# POWER.net
KiCad netlist of a schematic drawn in Altium Designer
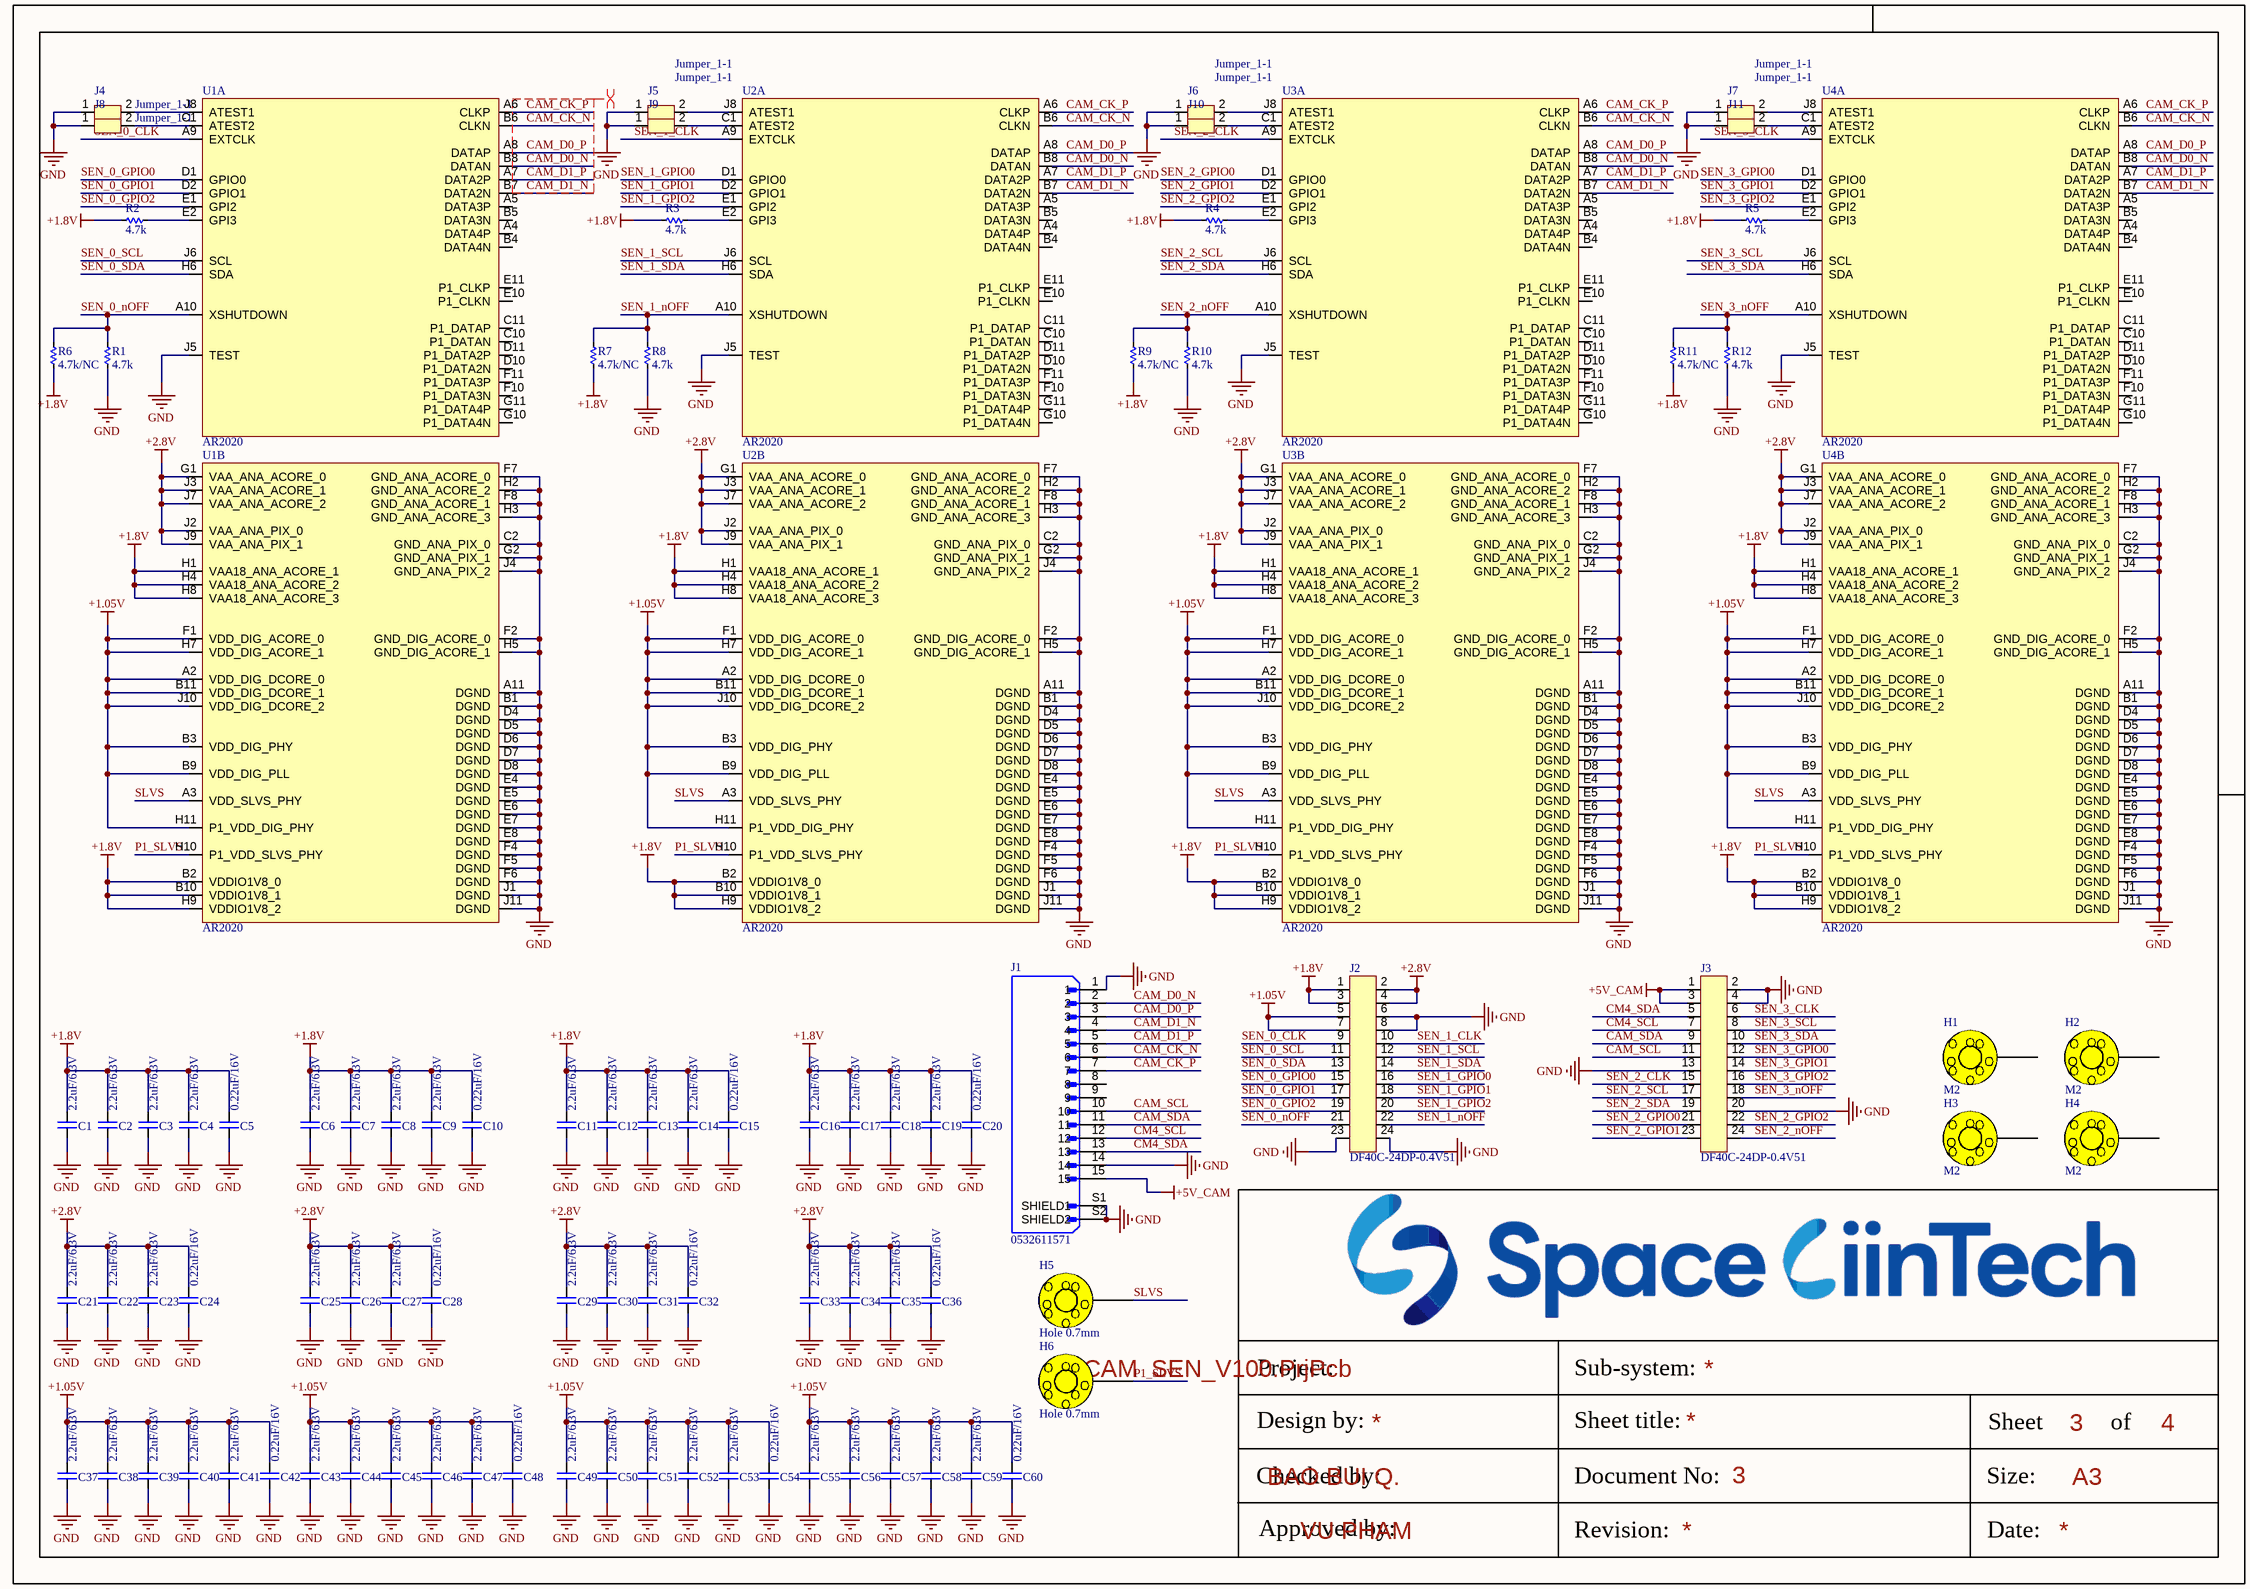
[diagram p0: POWER.SchDoc]

(export (version "E")
  (design (tool "Eeschema 10.0.6"))
  (components
    (comp (ref "C1")
      (value "2.2uF/6.3V")
      (footprint "CAP_C_1005X60")
      (description "CAP_Chip")
      (libsource (lib "LABLIB") (part "CAP_SMD"))
    )
    (comp (ref "C2")
      (value "2.2uF/6.3V")
      (footprint "CAP_C_1005X60")
      (description "CAP_Chip")
      (libsource (lib "LABLIB") (part "CAP_SMD"))
    )
    (comp (ref "C3")
      (value "2.2uF/6.3V")
      (footprint "CAP_C_1005X60")
      (description "CAP_Chip")
      (libsource (lib "LABLIB") (part "CAP_SMD"))
    )
    (comp (ref "C4")
      (value "2.2uF/6.3V")
      (footprint "CAP_C_1005X60")
      (description "CAP_Chip")
      (libsource (lib "LABLIB") (part "CAP_SMD"))
    )
    (comp (ref "C5")
      (value "0.22uF/16V")
      (footprint "CAP_C_1005X60")
      (description "CAP_Chip")
      (libsource (lib "LABLIB") (part "CAP_SMD"))
    )
    (comp (ref "C6")
      (value "2.2uF/6.3V")
      (footprint "CAP_C_1005X60")
      (description "CAP_Chip")
      (libsource (lib "LABLIB") (part "CAP_SMD"))
    )
    (comp (ref "C7")
      (value "2.2uF/6.3V")
      (footprint "CAP_C_1005X60")
      (description "CAP_Chip")
      (libsource (lib "LABLIB") (part "CAP_SMD"))
    )
    (comp (ref "C8")
      (value "2.2uF/6.3V")
      (footprint "CAP_C_1005X60")
      (description "CAP_Chip")
      (libsource (lib "LABLIB") (part "CAP_SMD"))
    )
    (comp (ref "C9")
      (value "2.2uF/6.3V")
      (footprint "CAP_C_1005X60")
      (description "CAP_Chip")
      (libsource (lib "LABLIB") (part "CAP_SMD"))
    )
    (comp (ref "C10")
      (value "0.22uF/16V")
      (footprint "CAP_C_1005X60")
      (description "CAP_Chip")
      (libsource (lib "LABLIB") (part "CAP_SMD"))
    )
    (comp (ref "C11")
      (value "2.2uF/6.3V")
      (footprint "CAP_C_1005X60")
      (description "CAP_Chip")
      (libsource (lib "LABLIB") (part "CAP_SMD"))
    )
    (comp (ref "C12")
      (value "2.2uF/6.3V")
      (footprint "CAP_C_1005X60")
      (description "CAP_Chip")
      (libsource (lib "LABLIB") (part "CAP_SMD"))
    )
    (comp (ref "C13")
      (value "2.2uF/6.3V")
      (footprint "CAP_C_1005X60")
      (description "CAP_Chip")
      (libsource (lib "LABLIB") (part "CAP_SMD"))
    )
    (comp (ref "C14")
      (value "2.2uF/6.3V")
      (footprint "CAP_C_1005X60")
      (description "CAP_Chip")
      (libsource (lib "LABLIB") (part "CAP_SMD"))
    )
    (comp (ref "C15")
      (value "0.22uF/16V")
      (footprint "CAP_C_1005X60")
      (description "CAP_Chip")
      (libsource (lib "LABLIB") (part "CAP_SMD"))
    )
    (comp (ref "C16")
      (value "2.2uF/6.3V")
      (footprint "CAP_C_1005X60")
      (description "CAP_Chip")
      (libsource (lib "LABLIB") (part "CAP_SMD"))
    )
    (comp (ref "C17")
      (value "2.2uF/6.3V")
      (footprint "CAP_C_1005X60")
      (description "CAP_Chip")
      (libsource (lib "LABLIB") (part "CAP_SMD"))
    )
    (comp (ref "C18")
      (value "2.2uF/6.3V")
      (footprint "CAP_C_1005X60")
      (description "CAP_Chip")
      (libsource (lib "LABLIB") (part "CAP_SMD"))
    )
    (comp (ref "C19")
      (value "2.2uF/6.3V")
      (footprint "CAP_C_1005X60")
      (description "CAP_Chip")
      (libsource (lib "LABLIB") (part "CAP_SMD"))
    )
    (comp (ref "C20")
      (value "0.22uF/16V")
      (footprint "CAP_C_1005X60")
      (description "CAP_Chip")
      (libsource (lib "LABLIB") (part "CAP_SMD"))
    )
    (comp (ref "C21")
      (value "2.2uF/6.3V")
      (footprint "CAP_C_1005X60")
      (description "CAP_Chip")
      (libsource (lib "LABLIB") (part "CAP_SMD"))
    )
    (comp (ref "C22")
      (value "2.2uF/6.3V")
      (footprint "CAP_C_1005X60")
      (description "CAP_Chip")
      (libsource (lib "LABLIB") (part "CAP_SMD"))
    )
    (comp (ref "C23")
      (value "2.2uF/6.3V")
      (footprint "CAP_C_1005X60")
      (description "CAP_Chip")
      (libsource (lib "LABLIB") (part "CAP_SMD"))
    )
    (comp (ref "C24")
      (value "0.22uF/16V")
      (footprint "CAP_C_1005X60")
      (description "CAP_Chip")
      (libsource (lib "LABLIB") (part "CAP_SMD"))
    )
    (comp (ref "C25")
      (value "2.2uF/6.3V")
      (footprint "CAP_C_1005X60")
      (description "CAP_Chip")
      (libsource (lib "LABLIB") (part "CAP_SMD"))
    )
    (comp (ref "C26")
      (value "2.2uF/6.3V")
      (footprint "CAP_C_1005X60")
      (description "CAP_Chip")
      (libsource (lib "LABLIB") (part "CAP_SMD"))
    )
    (comp (ref "C27")
      (value "2.2uF/6.3V")
      (footprint "CAP_C_1005X60")
      (description "CAP_Chip")
      (libsource (lib "LABLIB") (part "CAP_SMD"))
    )
    (comp (ref "C28")
      (value "0.22uF/16V")
      (footprint "CAP_C_1005X60")
      (description "CAP_Chip")
      (libsource (lib "LABLIB") (part "CAP_SMD"))
    )
    (comp (ref "C29")
      (value "2.2uF/6.3V")
      (footprint "CAP_C_1005X60")
      (description "CAP_Chip")
      (libsource (lib "LABLIB") (part "CAP_SMD"))
    )
    (comp (ref "C30")
      (value "2.2uF/6.3V")
      (footprint "CAP_C_1005X60")
      (description "CAP_Chip")
      (libsource (lib "LABLIB") (part "CAP_SMD"))
    )
    (comp (ref "C31")
      (value "2.2uF/6.3V")
      (footprint "CAP_C_1005X60")
      (description "CAP_Chip")
      (libsource (lib "LABLIB") (part "CAP_SMD"))
    )
    (comp (ref "C32")
      (value "0.22uF/16V")
      (footprint "CAP_C_1005X60")
      (description "CAP_Chip")
      (libsource (lib "LABLIB") (part "CAP_SMD"))
    )
    (comp (ref "C33")
      (value "2.2uF/6.3V")
      (footprint "CAP_C_1005X60")
      (description "CAP_Chip")
      (libsource (lib "LABLIB") (part "CAP_SMD"))
    )
    (comp (ref "C34")
      (value "2.2uF/6.3V")
      (footprint "CAP_C_1005X60")
      (description "CAP_Chip")
      (libsource (lib "LABLIB") (part "CAP_SMD"))
    )
    (comp (ref "C35")
      (value "2.2uF/6.3V")
      (footprint "CAP_C_1005X60")
      (description "CAP_Chip")
      (libsource (lib "LABLIB") (part "CAP_SMD"))
    )
    (comp (ref "C36")
      (value "0.22uF/16V")
      (footprint "CAP_C_1005X60")
      (description "CAP_Chip")
      (libsource (lib "LABLIB") (part "CAP_SMD"))
    )
    (comp (ref "C37")
      (value "2.2uF/6.3V")
      (footprint "CAP_C_1005X60")
      (description "CAP_Chip")
      (libsource (lib "LABLIB") (part "CAP_SMD"))
    )
    (comp (ref "C38")
      (value "2.2uF/6.3V")
      (footprint "CAP_C_1005X60")
      (description "CAP_Chip")
      (libsource (lib "LABLIB") (part "CAP_SMD"))
    )
    (comp (ref "C39")
      (value "2.2uF/6.3V")
      (footprint "CAP_C_1005X60")
      (description "CAP_Chip")
      (libsource (lib "LABLIB") (part "CAP_SMD"))
    )
    (comp (ref "C40")
      (value "2.2uF/6.3V")
      (footprint "CAP_C_1005X60")
      (description "CAP_Chip")
      (libsource (lib "LABLIB") (part "CAP_SMD"))
    )
    (comp (ref "C41")
      (value "2.2uF/6.3V")
      (footprint "CAP_C_1005X60")
      (description "CAP_Chip")
      (libsource (lib "LABLIB") (part "CAP_SMD"))
    )
    (comp (ref "C42")
      (value "0.22uF/16V")
      (footprint "CAP_C_1005X60")
      (description "CAP_Chip")
      (libsource (lib "LABLIB") (part "CAP_SMD"))
    )
    (comp (ref "C43")
      (value "2.2uF/6.3V")
      (footprint "CAP_C_1005X60")
      (description "CAP_Chip")
      (libsource (lib "LABLIB") (part "CAP_SMD"))
    )
    (comp (ref "C44")
      (value "2.2uF/6.3V")
      (footprint "CAP_C_1005X60")
      (description "CAP_Chip")
      (libsource (lib "LABLIB") (part "CAP_SMD"))
    )
    (comp (ref "C45")
      (value "2.2uF/6.3V")
      (footprint "CAP_C_1005X60")
      (description "CAP_Chip")
      (libsource (lib "LABLIB") (part "CAP_SMD"))
    )
    (comp (ref "C46")
      (value "2.2uF/6.3V")
      (footprint "CAP_C_1005X60")
      (description "CAP_Chip")
      (libsource (lib "LABLIB") (part "CAP_SMD"))
    )
    (comp (ref "C47")
      (value "2.2uF/6.3V")
      (footprint "CAP_C_1005X60")
      (description "CAP_Chip")
      (libsource (lib "LABLIB") (part "CAP_SMD"))
    )
    (comp (ref "C48")
      (value "0.22uF/16V")
      (footprint "CAP_C_1005X60")
      (description "CAP_Chip")
      (libsource (lib "LABLIB") (part "CAP_SMD"))
    )
    (comp (ref "C49")
      (value "2.2uF/6.3V")
      (footprint "CAP_C_1005X60")
      (description "CAP_Chip")
      (libsource (lib "LABLIB") (part "CAP_SMD"))
    )
    (comp (ref "C50")
      (value "2.2uF/6.3V")
      (footprint "CAP_C_1005X60")
      (description "CAP_Chip")
      (libsource (lib "LABLIB") (part "CAP_SMD"))
    )
    (comp (ref "C51")
      (value "2.2uF/6.3V")
      (footprint "CAP_C_1005X60")
      (description "CAP_Chip")
      (libsource (lib "LABLIB") (part "CAP_SMD"))
    )
    (comp (ref "C52")
      (value "2.2uF/6.3V")
      (footprint "CAP_C_1005X60")
      (description "CAP_Chip")
      (libsource (lib "LABLIB") (part "CAP_SMD"))
    )
    (comp (ref "C53")
      (value "2.2uF/6.3V")
      (footprint "CAP_C_1005X60")
      (description "CAP_Chip")
      (libsource (lib "LABLIB") (part "CAP_SMD"))
    )
    (comp (ref "C54")
      (value "0.22uF/16V")
      (footprint "CAP_C_1005X60")
      (description "CAP_Chip")
      (libsource (lib "LABLIB") (part "CAP_SMD"))
    )
    (comp (ref "C55")
      (value "2.2uF/6.3V")
      (footprint "CAP_C_1005X60")
      (description "CAP_Chip")
      (libsource (lib "LABLIB") (part "CAP_SMD"))
    )
    (comp (ref "C56")
      (value "2.2uF/6.3V")
      (footprint "CAP_C_1005X60")
      (description "CAP_Chip")
      (libsource (lib "LABLIB") (part "CAP_SMD"))
    )
    (comp (ref "C57")
      (value "2.2uF/6.3V")
      (footprint "CAP_C_1005X60")
      (description "CAP_Chip")
      (libsource (lib "LABLIB") (part "CAP_SMD"))
    )
    (comp (ref "C58")
      (value "2.2uF/6.3V")
      (footprint "CAP_C_1005X60")
      (description "CAP_Chip")
      (libsource (lib "LABLIB") (part "CAP_SMD"))
    )
    (comp (ref "C59")
      (value "2.2uF/6.3V")
      (footprint "CAP_C_1005X60")
      (description "CAP_Chip")
      (libsource (lib "LABLIB") (part "CAP_SMD"))
    )
    (comp (ref "C60")
      (value "0.22uF/16V")
      (footprint "CAP_C_1005X60")
      (description "CAP_Chip")
      (libsource (lib "LABLIB") (part "CAP_SMD"))
    )
    (comp (ref "H1") (value "M2") (footprint "HEX-2.2mm") (libsource (lib "hex_M3") (part "HEX-M3")))
    (comp (ref "H2") (value "M2") (footprint "HEX-2.2mm") (libsource (lib "hex_M3") (part "HEX-M3")))
    (comp (ref "H3") (value "M2") (footprint "HEX-2.2mm") (libsource (lib "hex_M3") (part "HEX-M3")))
    (comp (ref "H4") (value "M2") (footprint "HEX-2.2mm") (libsource (lib "hex_M3") (part "HEX-M3")))
    (comp (ref "H5") (value "Hole 0.7mm") (footprint "HEX-0.7mm") (libsource (lib "hex_M3") (part "HEX-M3")))
    (comp (ref "H6") (value "Hole 0.7mm") (footprint "HEX-0.7mm") (libsource (lib "hex_M3") (part "HEX-M3")))
    (comp (ref "J1")
      (value "0532611571")
      (footprint "0532611571")
      (description "Conn Shrouded Header (4 Sides) HDR 15 POS 1.25mm Solder RA Side Entry SMD PicoBladeâ„¢ T/R")
      (fields (field (name "MP") "532611571") (field (name "MF") "Molex"))
      (libsource (lib "EXP_HW_V2") (part "CONN_SMD_15"))
    )
    (comp (ref "J2")
      (value "DF40C-24DP-0.4V51")
      (footprint "CONN24_6p32X1p85")
      (description "No Description Available")
      (libsource (lib "CAMERA_SchLib") (part "DF40C-24DP-0.4V51"))
    )
    (comp (ref "J3")
      (value "DF40C-24DP-0.4V51")
      (footprint "CONN24_6p32X1p85")
      (description "No Description Available")
      (libsource (lib "CAMERA_SchLib") (part "DF40C-24DP-0.4V51"))
    )
    (comp (ref "J4")
      (value "Jumper_1-1")
      (footprint "Jumper_1-1")
      (libsource (lib "CAMERA_SchLib") (part "Jumper_1_1"))
    )
    (comp (ref "J5")
      (value "Jumper_1-1")
      (footprint "Jumper_1-1")
      (libsource (lib "CAMERA_SchLib") (part "Jumper_1_1"))
    )
    (comp (ref "J6")
      (value "Jumper_1-1")
      (footprint "Jumper_1-1")
      (libsource (lib "CAMERA_SchLib") (part "Jumper_1_1"))
    )
    (comp (ref "J7")
      (value "Jumper_1-1")
      (footprint "Jumper_1-1")
      (libsource (lib "CAMERA_SchLib") (part "Jumper_1_1"))
    )
    (comp (ref "J8")
      (value "Jumper_1-1")
      (footprint "Jumper_1-1")
      (libsource (lib "CAMERA_SchLib") (part "Jumper_1_1"))
    )
    (comp (ref "J9")
      (value "Jumper_1-1")
      (footprint "Jumper_1-1")
      (libsource (lib "CAMERA_SchLib") (part "Jumper_1_1"))
    )
    (comp (ref "J10")
      (value "Jumper_1-1")
      (footprint "Jumper_1-1")
      (libsource (lib "CAMERA_SchLib") (part "Jumper_1_1"))
    )
    (comp (ref "J11")
      (value "Jumper_1-1")
      (footprint "Jumper_1-1")
      (libsource (lib "CAMERA_SchLib") (part "Jumper_1_1"))
    )
    (comp (ref "R1")
      (value "4.7k")
      (footprint "RES_C_1005X40")
      (description "RES-Chip")
      (fields
        (field (name "MANUFACTURER") "Generic Components")
        (field (name "PUBLISHER") "Altium Hobart Technology Centre")
      )
      (libsource (lib "LABLIB") (part "RES-SMD"))
    )
    (comp (ref "R2")
      (value "4.7k")
      (footprint "RES_C_1005X40")
      (description "RES-Chip")
      (fields
        (field (name "MANUFACTURER") "Generic Components")
        (field (name "PUBLISHER") "Altium Hobart Technology Centre")
      )
      (libsource (lib "LABLIB") (part "RES-SMD"))
    )
    (comp (ref "R3")
      (value "4.7k")
      (footprint "RES_C_1005X40")
      (description "RES-Chip")
      (fields
        (field (name "MANUFACTURER") "Generic Components")
        (field (name "PUBLISHER") "Altium Hobart Technology Centre")
      )
      (libsource (lib "LABLIB") (part "RES-SMD"))
    )
    (comp (ref "R4")
      (value "4.7k")
      (footprint "RES_C_1005X40")
      (description "RES-Chip")
      (fields
        (field (name "MANUFACTURER") "Generic Components")
        (field (name "PUBLISHER") "Altium Hobart Technology Centre")
      )
      (libsource (lib "LABLIB") (part "RES-SMD"))
    )
    (comp (ref "R5")
      (value "4.7k")
      (footprint "RES_C_1005X40")
      (description "RES-Chip")
      (fields
        (field (name "MANUFACTURER") "Generic Components")
        (field (name "PUBLISHER") "Altium Hobart Technology Centre")
      )
      (libsource (lib "LABLIB") (part "RES-SMD"))
    )
    (comp (ref "R6")
      (value "4.7k/NC")
      (footprint "RES_C_1005X40")
      (description "RES-Chip")
      (fields
        (field (name "MANUFACTURER") "Generic Components")
        (field (name "PUBLISHER") "Altium Hobart Technology Centre")
      )
      (libsource (lib "LABLIB") (part "RES-SMD"))
    )
    (comp (ref "R7")
      (value "4.7k/NC")
      (footprint "RES_C_1005X40")
      (description "RES-Chip")
      (fields
        (field (name "MANUFACTURER") "Generic Components")
        (field (name "PUBLISHER") "Altium Hobart Technology Centre")
      )
      (libsource (lib "LABLIB") (part "RES-SMD"))
    )
    (comp (ref "R8")
      (value "4.7k")
      (footprint "RES_C_1005X40")
      (description "RES-Chip")
      (fields
        (field (name "MANUFACTURER") "Generic Components")
        (field (name "PUBLISHER") "Altium Hobart Technology Centre")
      )
      (libsource (lib "LABLIB") (part "RES-SMD"))
    )
    (comp (ref "R9")
      (value "4.7k/NC")
      (footprint "RES_C_1005X40")
      (description "RES-Chip")
      (fields
        (field (name "MANUFACTURER") "Generic Components")
        (field (name "PUBLISHER") "Altium Hobart Technology Centre")
      )
      (libsource (lib "LABLIB") (part "RES-SMD"))
    )
    (comp (ref "R10")
      (value "4.7k")
      (footprint "RES_C_1005X40")
      (description "RES-Chip")
      (fields
        (field (name "MANUFACTURER") "Generic Components")
        (field (name "PUBLISHER") "Altium Hobart Technology Centre")
      )
      (libsource (lib "LABLIB") (part "RES-SMD"))
    )
    (comp (ref "R11")
      (value "4.7k/NC")
      (footprint "RES_C_1005X40")
      (description "RES-Chip")
      (fields
        (field (name "MANUFACTURER") "Generic Components")
        (field (name "PUBLISHER") "Altium Hobart Technology Centre")
      )
      (libsource (lib "LABLIB") (part "RES-SMD"))
    )
    (comp (ref "R12")
      (value "4.7k")
      (footprint "RES_C_1005X40")
      (description "RES-Chip")
      (fields
        (field (name "MANUFACTURER") "Generic Components")
        (field (name "PUBLISHER") "Altium Hobart Technology Centre")
      )
      (libsource (lib "LABLIB") (part "RES-SMD"))
    )
    (comp (ref "U1")
      (value "AR2020")
      (footprint "BGA78C100P11X9_1300X1050X210")
      (libsource (lib "CAMERA_SchLib") (part "AR2020"))
    )
    (comp (ref "U2")
      (value "AR2020")
      (footprint "BGA78C100P11X9_1300X1050X210")
      (libsource (lib "CAMERA_SchLib") (part "AR2020"))
    )
    (comp (ref "U3")
      (value "AR2020")
      (footprint "BGA78C100P11X9_1300X1050X210")
      (libsource (lib "CAMERA_SchLib") (part "AR2020"))
    )
    (comp (ref "U4")
      (value "AR2020")
      (footprint "BGA78C100P11X9_1300X1050X210")
      (libsource (lib "CAMERA_SchLib") (part "AR2020"))
    )
  )
  (nets
    (net (code "1") (name "+1.05V") (class "Default")
      (node (ref "C37") (pin "2") (pinfunction "2_2") (pintype "passive"))
      (node (ref "C38") (pin "2") (pinfunction "2_2") (pintype "passive"))
      (node (ref "C39") (pin "2") (pinfunction "2_2") (pintype "passive"))
      (node (ref "C40") (pin "2") (pinfunction "2_2") (pintype "passive"))
      (node (ref "C41") (pin "2") (pinfunction "2_2") (pintype "passive"))
      (node (ref "C42") (pin "2") (pinfunction "2_2") (pintype "passive"))
      (node (ref "C43") (pin "2") (pinfunction "2_2") (pintype "passive"))
      (node (ref "C44") (pin "2") (pinfunction "2_2") (pintype "passive"))
      (node (ref "C45") (pin "2") (pinfunction "2_2") (pintype "passive"))
      (node (ref "C46") (pin "2") (pinfunction "2_2") (pintype "passive"))
      (node (ref "C47") (pin "2") (pinfunction "2_2") (pintype "passive"))
      (node (ref "C48") (pin "2") (pinfunction "2_2") (pintype "passive"))
      (node (ref "C49") (pin "2") (pinfunction "2_2") (pintype "passive"))
      (node (ref "C50") (pin "2") (pinfunction "2_2") (pintype "passive"))
      (node (ref "C51") (pin "2") (pinfunction "2_2") (pintype "passive"))
      (node (ref "C52") (pin "2") (pinfunction "2_2") (pintype "passive"))
      (node (ref "C53") (pin "2") (pinfunction "2_2") (pintype "passive"))
      (node (ref "C54") (pin "2") (pinfunction "2_2") (pintype "passive"))
      (node (ref "C55") (pin "2") (pinfunction "2_2") (pintype "passive"))
      (node (ref "C56") (pin "2") (pinfunction "2_2") (pintype "passive"))
      (node (ref "C57") (pin "2") (pinfunction "2_2") (pintype "passive"))
      (node (ref "C58") (pin "2") (pinfunction "2_2") (pintype "passive"))
      (node (ref "C59") (pin "2") (pinfunction "2_2") (pintype "passive"))
      (node (ref "C60") (pin "2") (pinfunction "2_2") (pintype "passive"))
      (node (ref "J2") (pin "5") (pintype "passive"))
      (node (ref "J2") (pin "7") (pintype "passive"))
      (node (ref "U1") (pin "A2") (pinfunction "VDD_DIG_DCORE_0_A2") (pintype "passive"))
      (node (ref "U1") (pin "B11") (pinfunction "VDD_DIG_DCORE_1_B11") (pintype "passive"))
      (node (ref "U1") (pin "B3") (pinfunction "VDD_DIG_PHY_B3") (pintype "passive"))
      (node (ref "U1") (pin "B9") (pinfunction "VDD_DIG_PLL_B9") (pintype "passive"))
      (node (ref "U1") (pin "F1") (pinfunction "VDD_DIG_ACORE_0_F1") (pintype "passive"))
      (node (ref "U1") (pin "H11") (pinfunction "P1_VDD_DIG_PHY_H11") (pintype "passive"))
      (node (ref "U1") (pin "H7") (pinfunction "VDD_DIG_ACORE_1_H7") (pintype "passive"))
      (node (ref "U1") (pin "J10") (pinfunction "VDD_DIG_DCORE_2_J10") (pintype "passive"))
      (node (ref "U2") (pin "A2") (pinfunction "VDD_DIG_DCORE_0_A2") (pintype "passive"))
      (node (ref "U2") (pin "B11") (pinfunction "VDD_DIG_DCORE_1_B11") (pintype "passive"))
      (node (ref "U2") (pin "B3") (pinfunction "VDD_DIG_PHY_B3") (pintype "passive"))
      (node (ref "U2") (pin "B9") (pinfunction "VDD_DIG_PLL_B9") (pintype "passive"))
      (node (ref "U2") (pin "F1") (pinfunction "VDD_DIG_ACORE_0_F1") (pintype "passive"))
      (node (ref "U2") (pin "H11") (pinfunction "P1_VDD_DIG_PHY_H11") (pintype "passive"))
      (node (ref "U2") (pin "H7") (pinfunction "VDD_DIG_ACORE_1_H7") (pintype "passive"))
      (node (ref "U2") (pin "J10") (pinfunction "VDD_DIG_DCORE_2_J10") (pintype "passive"))
      (node (ref "U3") (pin "A2") (pinfunction "VDD_DIG_DCORE_0_A2") (pintype "passive"))
      (node (ref "U3") (pin "B11") (pinfunction "VDD_DIG_DCORE_1_B11") (pintype "passive"))
      (node (ref "U3") (pin "B3") (pinfunction "VDD_DIG_PHY_B3") (pintype "passive"))
      (node (ref "U3") (pin "B9") (pinfunction "VDD_DIG_PLL_B9") (pintype "passive"))
      (node (ref "U3") (pin "F1") (pinfunction "VDD_DIG_ACORE_0_F1") (pintype "passive"))
      (node (ref "U3") (pin "H11") (pinfunction "P1_VDD_DIG_PHY_H11") (pintype "passive"))
      (node (ref "U3") (pin "H7") (pinfunction "VDD_DIG_ACORE_1_H7") (pintype "passive"))
      (node (ref "U3") (pin "J10") (pinfunction "VDD_DIG_DCORE_2_J10") (pintype "passive"))
      (node (ref "U4") (pin "A2") (pinfunction "VDD_DIG_DCORE_0_A2") (pintype "passive"))
      (node (ref "U4") (pin "B11") (pinfunction "VDD_DIG_DCORE_1_B11") (pintype "passive"))
      (node (ref "U4") (pin "B3") (pinfunction "VDD_DIG_PHY_B3") (pintype "passive"))
      (node (ref "U4") (pin "B9") (pinfunction "VDD_DIG_PLL_B9") (pintype "passive"))
      (node (ref "U4") (pin "F1") (pinfunction "VDD_DIG_ACORE_0_F1") (pintype "passive"))
      (node (ref "U4") (pin "H11") (pinfunction "P1_VDD_DIG_PHY_H11") (pintype "passive"))
      (node (ref "U4") (pin "H7") (pinfunction "VDD_DIG_ACORE_1_H7") (pintype "passive"))
      (node (ref "U4") (pin "J10") (pinfunction "VDD_DIG_DCORE_2_J10") (pintype "passive"))
    )
    (net (code "2") (name "+1.8V") (class "Default")
      (node (ref "C1") (pin "2") (pinfunction "2_2") (pintype "passive"))
      (node (ref "C10") (pin "2") (pinfunction "2_2") (pintype "passive"))
      (node (ref "C11") (pin "2") (pinfunction "2_2") (pintype "passive"))
      (node (ref "C12") (pin "2") (pinfunction "2_2") (pintype "passive"))
      (node (ref "C13") (pin "2") (pinfunction "2_2") (pintype "passive"))
      (node (ref "C14") (pin "2") (pinfunction "2_2") (pintype "passive"))
      (node (ref "C15") (pin "2") (pinfunction "2_2") (pintype "passive"))
      (node (ref "C16") (pin "2") (pinfunction "2_2") (pintype "passive"))
      (node (ref "C17") (pin "2") (pinfunction "2_2") (pintype "passive"))
      (node (ref "C18") (pin "2") (pinfunction "2_2") (pintype "passive"))
      (node (ref "C19") (pin "2") (pinfunction "2_2") (pintype "passive"))
      (node (ref "C2") (pin "2") (pinfunction "2_2") (pintype "passive"))
      (node (ref "C20") (pin "2") (pinfunction "2_2") (pintype "passive"))
      (node (ref "C3") (pin "2") (pinfunction "2_2") (pintype "passive"))
      (node (ref "C4") (pin "2") (pinfunction "2_2") (pintype "passive"))
      (node (ref "C5") (pin "2") (pinfunction "2_2") (pintype "passive"))
      (node (ref "C6") (pin "2") (pinfunction "2_2") (pintype "passive"))
      (node (ref "C7") (pin "2") (pinfunction "2_2") (pintype "passive"))
      (node (ref "C8") (pin "2") (pinfunction "2_2") (pintype "passive"))
      (node (ref "C9") (pin "2") (pinfunction "2_2") (pintype "passive"))
      (node (ref "J2") (pin "1") (pintype "passive"))
      (node (ref "J2") (pin "3") (pintype "passive"))
      (node (ref "R11") (pin "1") (pinfunction "1_1") (pintype "passive"))
      (node (ref "R2") (pin "1") (pinfunction "1_1") (pintype "passive"))
      (node (ref "R3") (pin "1") (pinfunction "1_1") (pintype "passive"))
      (node (ref "R4") (pin "1") (pinfunction "1_1") (pintype "passive"))
      (node (ref "R5") (pin "1") (pinfunction "1_1") (pintype "passive"))
      (node (ref "R6") (pin "1") (pinfunction "1_1") (pintype "passive"))
      (node (ref "R7") (pin "1") (pinfunction "1_1") (pintype "passive"))
      (node (ref "R9") (pin "1") (pinfunction "1_1") (pintype "passive"))
      (node (ref "U1") (pin "B10") (pinfunction "VDDIO1V8_1_B10") (pintype "passive"))
      (node (ref "U1") (pin "B2") (pinfunction "VDDIO1V8_0_B2") (pintype "passive"))
      (node (ref "U1") (pin "H1") (pinfunction "VAA18_ANA_ACORE_1_H1") (pintype "passive"))
      (node (ref "U1") (pin "H4") (pinfunction "VAA18_ANA_ACORE_2_H4") (pintype "passive"))
      (node (ref "U1") (pin "H8") (pinfunction "VAA18_ANA_ACORE_3_H8") (pintype "passive"))
      (node (ref "U1") (pin "H9") (pinfunction "VDDIO1V8_2_H9") (pintype "passive"))
      (node (ref "U2") (pin "B10") (pinfunction "VDDIO1V8_1_B10") (pintype "passive"))
      (node (ref "U2") (pin "B2") (pinfunction "VDDIO1V8_0_B2") (pintype "passive"))
      (node (ref "U2") (pin "H1") (pinfunction "VAA18_ANA_ACORE_1_H1") (pintype "passive"))
      (node (ref "U2") (pin "H4") (pinfunction "VAA18_ANA_ACORE_2_H4") (pintype "passive"))
      (node (ref "U2") (pin "H8") (pinfunction "VAA18_ANA_ACORE_3_H8") (pintype "passive"))
      (node (ref "U2") (pin "H9") (pinfunction "VDDIO1V8_2_H9") (pintype "passive"))
      (node (ref "U3") (pin "B10") (pinfunction "VDDIO1V8_1_B10") (pintype "passive"))
      (node (ref "U3") (pin "B2") (pinfunction "VDDIO1V8_0_B2") (pintype "passive"))
      (node (ref "U3") (pin "H1") (pinfunction "VAA18_ANA_ACORE_1_H1") (pintype "passive"))
      (node (ref "U3") (pin "H4") (pinfunction "VAA18_ANA_ACORE_2_H4") (pintype "passive"))
      (node (ref "U3") (pin "H8") (pinfunction "VAA18_ANA_ACORE_3_H8") (pintype "passive"))
      (node (ref "U3") (pin "H9") (pinfunction "VDDIO1V8_2_H9") (pintype "passive"))
      (node (ref "U4") (pin "B10") (pinfunction "VDDIO1V8_1_B10") (pintype "passive"))
      (node (ref "U4") (pin "B2") (pinfunction "VDDIO1V8_0_B2") (pintype "passive"))
      (node (ref "U4") (pin "H1") (pinfunction "VAA18_ANA_ACORE_1_H1") (pintype "passive"))
      (node (ref "U4") (pin "H4") (pinfunction "VAA18_ANA_ACORE_2_H4") (pintype "passive"))
      (node (ref "U4") (pin "H8") (pinfunction "VAA18_ANA_ACORE_3_H8") (pintype "passive"))
      (node (ref "U4") (pin "H9") (pinfunction "VDDIO1V8_2_H9") (pintype "passive"))
    )
    (net (code "3") (name "+2.8V") (class "Default")
      (node (ref "C21") (pin "2") (pinfunction "2_2") (pintype "passive"))
      (node (ref "C22") (pin "2") (pinfunction "2_2") (pintype "passive"))
      (node (ref "C23") (pin "2") (pinfunction "2_2") (pintype "passive"))
      (node (ref "C24") (pin "2") (pinfunction "2_2") (pintype "passive"))
      (node (ref "C25") (pin "2") (pinfunction "2_2") (pintype "passive"))
      (node (ref "C26") (pin "2") (pinfunction "2_2") (pintype "passive"))
      (node (ref "C27") (pin "2") (pinfunction "2_2") (pintype "passive"))
      (node (ref "C28") (pin "2") (pinfunction "2_2") (pintype "passive"))
      (node (ref "C29") (pin "2") (pinfunction "2_2") (pintype "passive"))
      (node (ref "C30") (pin "2") (pinfunction "2_2") (pintype "passive"))
      (node (ref "C31") (pin "2") (pinfunction "2_2") (pintype "passive"))
      (node (ref "C32") (pin "2") (pinfunction "2_2") (pintype "passive"))
      (node (ref "C33") (pin "2") (pinfunction "2_2") (pintype "passive"))
      (node (ref "C34") (pin "2") (pinfunction "2_2") (pintype "passive"))
      (node (ref "C35") (pin "2") (pinfunction "2_2") (pintype "passive"))
      (node (ref "C36") (pin "2") (pinfunction "2_2") (pintype "passive"))
      (node (ref "J2") (pin "2") (pintype "passive"))
      (node (ref "J2") (pin "4") (pintype "passive"))
      (node (ref "U1") (pin "G1") (pinfunction "VAA_ANA_ACORE_0_G1") (pintype "passive"))
      (node (ref "U1") (pin "J2") (pinfunction "VAA_ANA_PIX_0_J2") (pintype "passive"))
      (node (ref "U1") (pin "J3") (pinfunction "VAA_ANA_ACORE_1_J3") (pintype "passive"))
      (node (ref "U1") (pin "J7") (pinfunction "VAA_ANA_ACORE_2_J7") (pintype "passive"))
      (node (ref "U1") (pin "J9") (pinfunction "VAA_ANA_PIX_1_J9") (pintype "passive"))
      (node (ref "U2") (pin "G1") (pinfunction "VAA_ANA_ACORE_0_G1") (pintype "passive"))
      (node (ref "U2") (pin "J2") (pinfunction "VAA_ANA_PIX_0_J2") (pintype "passive"))
      (node (ref "U2") (pin "J3") (pinfunction "VAA_ANA_ACORE_1_J3") (pintype "passive"))
      (node (ref "U2") (pin "J7") (pinfunction "VAA_ANA_ACORE_2_J7") (pintype "passive"))
      (node (ref "U2") (pin "J9") (pinfunction "VAA_ANA_PIX_1_J9") (pintype "passive"))
      (node (ref "U3") (pin "G1") (pinfunction "VAA_ANA_ACORE_0_G1") (pintype "passive"))
      (node (ref "U3") (pin "J2") (pinfunction "VAA_ANA_PIX_0_J2") (pintype "passive"))
      (node (ref "U3") (pin "J3") (pinfunction "VAA_ANA_ACORE_1_J3") (pintype "passive"))
      (node (ref "U3") (pin "J7") (pinfunction "VAA_ANA_ACORE_2_J7") (pintype "passive"))
      (node (ref "U3") (pin "J9") (pinfunction "VAA_ANA_PIX_1_J9") (pintype "passive"))
      (node (ref "U4") (pin "G1") (pinfunction "VAA_ANA_ACORE_0_G1") (pintype "passive"))
      (node (ref "U4") (pin "J2") (pinfunction "VAA_ANA_PIX_0_J2") (pintype "passive"))
      (node (ref "U4") (pin "J3") (pinfunction "VAA_ANA_ACORE_1_J3") (pintype "passive"))
      (node (ref "U4") (pin "J7") (pinfunction "VAA_ANA_ACORE_2_J7") (pintype "passive"))
      (node (ref "U4") (pin "J9") (pinfunction "VAA_ANA_PIX_1_J9") (pintype "passive"))
    )
    (net (code "4") (name "+5V_CAM") (class "Default")
      (node (ref "J1") (pin "15") (pinfunction "15_15") (pintype "passive"))
      (node (ref "J3") (pin "1") (pintype "passive"))
      (node (ref "J3") (pin "3") (pintype "passive"))
    )
    (net (code "5") (name "/CAM_CK_N") (class "Default")
      (node (ref "J1") (pin "6") (pinfunction "6_6") (pintype "passive"))
      (node (ref "U1") (pin "B6") (pinfunction "CLKN_B6") (pintype "passive"))
      (node (ref "U2") (pin "B6") (pinfunction "CLKN_B6") (pintype "passive"))
      (node (ref "U3") (pin "B6") (pinfunction "CLKN_B6") (pintype "passive"))
      (node (ref "U4") (pin "B6") (pinfunction "CLKN_B6") (pintype "passive"))
    )
    (net (code "6") (name "/CAM_CK_P") (class "Default")
      (node (ref "J1") (pin "7") (pinfunction "7_7") (pintype "passive"))
      (node (ref "U1") (pin "A6") (pinfunction "CLKP_A6") (pintype "passive"))
      (node (ref "U2") (pin "A6") (pinfunction "CLKP_A6") (pintype "passive"))
      (node (ref "U3") (pin "A6") (pinfunction "CLKP_A6") (pintype "passive"))
      (node (ref "U4") (pin "A6") (pinfunction "CLKP_A6") (pintype "passive"))
    )
    (net (code "7") (name "/CAM_D0_N") (class "Default")
      (node (ref "J1") (pin "2") (pinfunction "2_2") (pintype "passive"))
      (node (ref "U1") (pin "B8") (pinfunction "DATAN_B8") (pintype "passive"))
      (node (ref "U2") (pin "B8") (pinfunction "DATAN_B8") (pintype "passive"))
      (node (ref "U3") (pin "B8") (pinfunction "DATAN_B8") (pintype "passive"))
      (node (ref "U4") (pin "B8") (pinfunction "DATAN_B8") (pintype "passive"))
    )
    (net (code "8") (name "/CAM_D0_P") (class "Default")
      (node (ref "J1") (pin "3") (pinfunction "3_3") (pintype "passive"))
      (node (ref "U1") (pin "A8") (pinfunction "DATAP_A8") (pintype "passive"))
      (node (ref "U2") (pin "A8") (pinfunction "DATAP_A8") (pintype "passive"))
      (node (ref "U3") (pin "A8") (pinfunction "DATAP_A8") (pintype "passive"))
      (node (ref "U4") (pin "A8") (pinfunction "DATAP_A8") (pintype "passive"))
    )
    (net (code "9") (name "/CAM_D1_N") (class "Default")
      (node (ref "J1") (pin "4") (pinfunction "4_4") (pintype "passive"))
      (node (ref "U1") (pin "B7") (pinfunction "DATA2N_B7") (pintype "passive"))
      (node (ref "U2") (pin "B7") (pinfunction "DATA2N_B7") (pintype "passive"))
      (node (ref "U3") (pin "B7") (pinfunction "DATA2N_B7") (pintype "passive"))
      (node (ref "U4") (pin "B7") (pinfunction "DATA2N_B7") (pintype "passive"))
    )
    (net (code "10") (name "/CAM_D1_P") (class "Default")
      (node (ref "J1") (pin "5") (pinfunction "5_5") (pintype "passive"))
      (node (ref "U1") (pin "A7") (pinfunction "DATA2P_A7") (pintype "passive"))
      (node (ref "U2") (pin "A7") (pinfunction "DATA2P_A7") (pintype "passive"))
      (node (ref "U3") (pin "A7") (pinfunction "DATA2P_A7") (pintype "passive"))
      (node (ref "U4") (pin "A7") (pinfunction "DATA2P_A7") (pintype "passive"))
    )
    (net (code "11") (name "/CAM_SCL") (class "Default")
      (node (ref "J1") (pin "10") (pinfunction "10_10") (pintype "passive"))
      (node (ref "J3") (pin "11") (pintype "passive"))
    )
    (net (code "12") (name "/CAM_SDA") (class "Default")
      (node (ref "J1") (pin "11") (pinfunction "11_11") (pintype "passive"))
      (node (ref "J3") (pin "9") (pintype "passive"))
    )
    (net (code "13") (name "/CM4_SCL") (class "Default")
      (node (ref "J1") (pin "12") (pinfunction "12_12") (pintype "passive"))
      (node (ref "J3") (pin "7") (pintype "passive"))
    )
    (net (code "14") (name "/CM4_SDA") (class "Default")
      (node (ref "J1") (pin "13") (pinfunction "13_13") (pintype "passive"))
      (node (ref "J3") (pin "5") (pintype "passive"))
    )
    (net (code "15") (name "/P1_SLVS") (class "Default")
      (node (ref "H6") (pin "1") (pinfunction "1_1") (pintype "power_in"))
      (node (ref "U1") (pin "H10") (pinfunction "P1_VDD_SLVS_PHY_H10") (pintype "passive"))
      (node (ref "U2") (pin "H10") (pinfunction "P1_VDD_SLVS_PHY_H10") (pintype "passive"))
      (node (ref "U3") (pin "H10") (pinfunction "P1_VDD_SLVS_PHY_H10") (pintype "passive"))
      (node (ref "U4") (pin "H10") (pinfunction "P1_VDD_SLVS_PHY_H10") (pintype "passive"))
    )
    (net (code "16") (name "/SEN_0_CLK") (class "Default")
      (node (ref "J2") (pin "9") (pintype "passive"))
      (node (ref "U1") (pin "A9") (pinfunction "EXTCLK_A9") (pintype "passive"))
    )
    (net (code "17") (name "/SEN_0_GPIO0") (class "Default")
      (node (ref "J2") (pin "15") (pintype "passive"))
      (node (ref "U1") (pin "D1") (pinfunction "GPIO0_D1") (pintype "passive"))
    )
    (net (code "18") (name "/SEN_0_GPIO1") (class "Default")
      (node (ref "J2") (pin "17") (pintype "passive"))
      (node (ref "U1") (pin "D2") (pinfunction "GPIO1_D2") (pintype "passive"))
    )
    (net (code "19") (name "/SEN_0_GPIO2") (class "Default")
      (node (ref "J2") (pin "19") (pintype "passive"))
      (node (ref "U1") (pin "E1") (pinfunction "GPI2_E1") (pintype "passive"))
    )
    (net (code "20") (name "/SEN_0_SCL") (class "Default")
      (node (ref "J2") (pin "11") (pintype "passive"))
      (node (ref "U1") (pin "J6") (pinfunction "SCL_J6") (pintype "passive"))
    )
    (net (code "21") (name "/SEN_0_SDA") (class "Default")
      (node (ref "J2") (pin "13") (pintype "passive"))
      (node (ref "U1") (pin "H6") (pinfunction "SDA_H6") (pintype "passive"))
    )
    (net (code "22") (name "/SEN_0_nOFF") (class "Default")
      (node (ref "J2") (pin "21") (pintype "passive"))
      (node (ref "R1") (pin "1") (pinfunction "1_1") (pintype "passive"))
      (node (ref "R6") (pin "2") (pinfunction "2_2") (pintype "passive"))
      (node (ref "U1") (pin "A10") (pinfunction "XSHUTDOWN_A10") (pintype "passive"))
    )
    (net (code "23") (name "/SEN_1_CLK") (class "Default")
      (node (ref "J2") (pin "10") (pintype "passive"))
      (node (ref "U2") (pin "A9") (pinfunction "EXTCLK_A9") (pintype "passive"))
    )
    (net (code "24") (name "/SEN_1_GPIO0") (class "Default")
      (node (ref "J2") (pin "16") (pintype "passive"))
      (node (ref "U2") (pin "D1") (pinfunction "GPIO0_D1") (pintype "passive"))
    )
    (net (code "25") (name "/SEN_1_GPIO1") (class "Default")
      (node (ref "J2") (pin "18") (pintype "passive"))
      (node (ref "U2") (pin "D2") (pinfunction "GPIO1_D2") (pintype "passive"))
    )
    (net (code "26") (name "/SEN_1_GPIO2") (class "Default")
      (node (ref "J2") (pin "20") (pintype "passive"))
      (node (ref "U2") (pin "E1") (pinfunction "GPI2_E1") (pintype "passive"))
    )
    (net (code "27") (name "/SEN_1_SCL") (class "Default")
      (node (ref "J2") (pin "12") (pintype "passive"))
      (node (ref "U2") (pin "J6") (pinfunction "SCL_J6") (pintype "passive"))
    )
    (net (code "28") (name "/SEN_1_SDA") (class "Default")
      (node (ref "J2") (pin "14") (pintype "passive"))
      (node (ref "U2") (pin "H6") (pinfunction "SDA_H6") (pintype "passive"))
    )
    (net (code "29") (name "/SEN_1_nOFF") (class "Default")
      (node (ref "J2") (pin "22") (pintype "passive"))
      (node (ref "R7") (pin "2") (pinfunction "2_2") (pintype "passive"))
      (node (ref "R8") (pin "1") (pinfunction "1_1") (pintype "passive"))
      (node (ref "U2") (pin "A10") (pinfunction "XSHUTDOWN_A10") (pintype "passive"))
    )
    (net (code "30") (name "/SEN_2_CLK") (class "Default")
      (node (ref "J3") (pin "15") (pintype "passive"))
      (node (ref "U3") (pin "A9") (pinfunction "EXTCLK_A9") (pintype "passive"))
    )
    (net (code "31") (name "/SEN_2_GPIO0") (class "Default")
      (node (ref "J3") (pin "21") (pintype "passive"))
      (node (ref "U3") (pin "D1") (pinfunction "GPIO0_D1") (pintype "passive"))
    )
    (net (code "32") (name "/SEN_2_GPIO1") (class "Default")
      (node (ref "J3") (pin "23") (pintype "passive"))
      (node (ref "U3") (pin "D2") (pinfunction "GPIO1_D2") (pintype "passive"))
    )
    (net (code "33") (name "/SEN_2_GPIO2") (class "Default")
      (node (ref "J3") (pin "22") (pintype "passive"))
      (node (ref "U3") (pin "E1") (pinfunction "GPI2_E1") (pintype "passive"))
    )
    (net (code "34") (name "/SEN_2_SCL") (class "Default")
      (node (ref "J3") (pin "17") (pintype "passive"))
      (node (ref "U3") (pin "J6") (pinfunction "SCL_J6") (pintype "passive"))
    )
    (net (code "35") (name "/SEN_2_SDA") (class "Default")
      (node (ref "J3") (pin "19") (pintype "passive"))
      (node (ref "U3") (pin "H6") (pinfunction "SDA_H6") (pintype "passive"))
    )
    (net (code "36") (name "/SEN_2_nOFF") (class "Default")
      (node (ref "J3") (pin "24") (pintype "passive"))
      (node (ref "R10") (pin "1") (pinfunction "1_1") (pintype "passive"))
      (node (ref "R9") (pin "2") (pinfunction "2_2") (pintype "passive"))
      (node (ref "U3") (pin "A10") (pinfunction "XSHUTDOWN_A10") (pintype "passive"))
    )
    (net (code "37") (name "/SEN_3_CLK") (class "Default")
      (node (ref "J3") (pin "6") (pintype "passive"))
      (node (ref "U4") (pin "A9") (pinfunction "EXTCLK_A9") (pintype "passive"))
    )
    (net (code "38") (name "/SEN_3_GPIO0") (class "Default")
      (node (ref "J3") (pin "12") (pintype "passive"))
      (node (ref "U4") (pin "D1") (pinfunction "GPIO0_D1") (pintype "passive"))
    )
    (net (code "39") (name "/SEN_3_GPIO1") (class "Default")
      (node (ref "J3") (pin "14") (pintype "passive"))
      (node (ref "U4") (pin "D2") (pinfunction "GPIO1_D2") (pintype "passive"))
    )
    (net (code "40") (name "/SEN_3_GPIO2") (class "Default")
      (node (ref "J3") (pin "16") (pintype "passive"))
      (node (ref "U4") (pin "E1") (pinfunction "GPI2_E1") (pintype "passive"))
    )
    (net (code "41") (name "/SEN_3_SCL") (class "Default")
      (node (ref "J3") (pin "8") (pintype "passive"))
      (node (ref "U4") (pin "J6") (pinfunction "SCL_J6") (pintype "passive"))
    )
    (net (code "42") (name "/SEN_3_SDA") (class "Default")
      (node (ref "J3") (pin "10") (pintype "passive"))
      (node (ref "U4") (pin "H6") (pinfunction "SDA_H6") (pintype "passive"))
    )
    (net (code "43") (name "/SEN_3_nOFF") (class "Default")
      (node (ref "J3") (pin "18") (pintype "passive"))
      (node (ref "R11") (pin "2") (pinfunction "2_2") (pintype "passive"))
      (node (ref "R12") (pin "1") (pinfunction "1_1") (pintype "passive"))
      (node (ref "U4") (pin "A10") (pinfunction "XSHUTDOWN_A10") (pintype "passive"))
    )
    (net (code "44") (name "/SLVS") (class "Default")
      (node (ref "H5") (pin "1") (pinfunction "1_1") (pintype "power_in"))
      (node (ref "U1") (pin "A3") (pinfunction "VDD_SLVS_PHY_A3") (pintype "passive"))
      (node (ref "U2") (pin "A3") (pinfunction "VDD_SLVS_PHY_A3") (pintype "passive"))
      (node (ref "U3") (pin "A3") (pinfunction "VDD_SLVS_PHY_A3") (pintype "passive"))
      (node (ref "U4") (pin "A3") (pinfunction "VDD_SLVS_PHY_A3") (pintype "passive"))
    )
    (net (code "45") (name "GND") (class "Default")
      (node (ref "C1") (pin "1") (pinfunction "1_1") (pintype "passive"))
      (node (ref "C10") (pin "1") (pinfunction "1_1") (pintype "passive"))
      (node (ref "C11") (pin "1") (pinfunction "1_1") (pintype "passive"))
      (node (ref "C12") (pin "1") (pinfunction "1_1") (pintype "passive"))
      (node (ref "C13") (pin "1") (pinfunction "1_1") (pintype "passive"))
      (node (ref "C14") (pin "1") (pinfunction "1_1") (pintype "passive"))
      (node (ref "C15") (pin "1") (pinfunction "1_1") (pintype "passive"))
      (node (ref "C16") (pin "1") (pinfunction "1_1") (pintype "passive"))
      (node (ref "C17") (pin "1") (pinfunction "1_1") (pintype "passive"))
      (node (ref "C18") (pin "1") (pinfunction "1_1") (pintype "passive"))
      (node (ref "C19") (pin "1") (pinfunction "1_1") (pintype "passive"))
      (node (ref "C2") (pin "1") (pinfunction "1_1") (pintype "passive"))
      (node (ref "C20") (pin "1") (pinfunction "1_1") (pintype "passive"))
      (node (ref "C21") (pin "1") (pinfunction "1_1") (pintype "passive"))
      (node (ref "C22") (pin "1") (pinfunction "1_1") (pintype "passive"))
      (node (ref "C23") (pin "1") (pinfunction "1_1") (pintype "passive"))
      (node (ref "C24") (pin "1") (pinfunction "1_1") (pintype "passive"))
      (node (ref "C25") (pin "1") (pinfunction "1_1") (pintype "passive"))
      (node (ref "C26") (pin "1") (pinfunction "1_1") (pintype "passive"))
      (node (ref "C27") (pin "1") (pinfunction "1_1") (pintype "passive"))
      (node (ref "C28") (pin "1") (pinfunction "1_1") (pintype "passive"))
      (node (ref "C29") (pin "1") (pinfunction "1_1") (pintype "passive"))
      (node (ref "C3") (pin "1") (pinfunction "1_1") (pintype "passive"))
      (node (ref "C30") (pin "1") (pinfunction "1_1") (pintype "passive"))
      (node (ref "C31") (pin "1") (pinfunction "1_1") (pintype "passive"))
      (node (ref "C32") (pin "1") (pinfunction "1_1") (pintype "passive"))
      (node (ref "C33") (pin "1") (pinfunction "1_1") (pintype "passive"))
      (node (ref "C34") (pin "1") (pinfunction "1_1") (pintype "passive"))
      (node (ref "C35") (pin "1") (pinfunction "1_1") (pintype "passive"))
      (node (ref "C36") (pin "1") (pinfunction "1_1") (pintype "passive"))
      (node (ref "C37") (pin "1") (pinfunction "1_1") (pintype "passive"))
      (node (ref "C38") (pin "1") (pinfunction "1_1") (pintype "passive"))
      (node (ref "C39") (pin "1") (pinfunction "1_1") (pintype "passive"))
      (node (ref "C4") (pin "1") (pinfunction "1_1") (pintype "passive"))
      (node (ref "C40") (pin "1") (pinfunction "1_1") (pintype "passive"))
      (node (ref "C41") (pin "1") (pinfunction "1_1") (pintype "passive"))
      (node (ref "C42") (pin "1") (pinfunction "1_1") (pintype "passive"))
      (node (ref "C43") (pin "1") (pinfunction "1_1") (pintype "passive"))
      (node (ref "C44") (pin "1") (pinfunction "1_1") (pintype "passive"))
      (node (ref "C45") (pin "1") (pinfunction "1_1") (pintype "passive"))
      (node (ref "C46") (pin "1") (pinfunction "1_1") (pintype "passive"))
      (node (ref "C47") (pin "1") (pinfunction "1_1") (pintype "passive"))
      (node (ref "C48") (pin "1") (pinfunction "1_1") (pintype "passive"))
      (node (ref "C49") (pin "1") (pinfunction "1_1") (pintype "passive"))
      (node (ref "C5") (pin "1") (pinfunction "1_1") (pintype "passive"))
      (node (ref "C50") (pin "1") (pinfunction "1_1") (pintype "passive"))
      (node (ref "C51") (pin "1") (pinfunction "1_1") (pintype "passive"))
      (node (ref "C52") (pin "1") (pinfunction "1_1") (pintype "passive"))
      (node (ref "C53") (pin "1") (pinfunction "1_1") (pintype "passive"))
      (node (ref "C54") (pin "1") (pinfunction "1_1") (pintype "passive"))
      (node (ref "C55") (pin "1") (pinfunction "1_1") (pintype "passive"))
      (node (ref "C56") (pin "1") (pinfunction "1_1") (pintype "passive"))
      (node (ref "C57") (pin "1") (pinfunction "1_1") (pintype "passive"))
      (node (ref "C58") (pin "1") (pinfunction "1_1") (pintype "passive"))
      (node (ref "C59") (pin "1") (pinfunction "1_1") (pintype "passive"))
      (node (ref "C6") (pin "1") (pinfunction "1_1") (pintype "passive"))
      (node (ref "C60") (pin "1") (pinfunction "1_1") (pintype "passive"))
      (node (ref "C7") (pin "1") (pinfunction "1_1") (pintype "passive"))
      (node (ref "C8") (pin "1") (pinfunction "1_1") (pintype "passive"))
      (node (ref "C9") (pin "1") (pinfunction "1_1") (pintype "passive"))
      (node (ref "J1") (pin "1") (pinfunction "1_1") (pintype "passive"))
      (node (ref "J1") (pin "14") (pinfunction "14_14") (pintype "passive"))
      (node (ref "J1") (pin "S1") (pinfunction "SHIELD1_S1") (pintype "passive"))
      (node (ref "J1") (pin "S2") (pinfunction "SHIELD2_S2") (pintype "passive"))
      (node (ref "J10") (pin "1") (pintype "passive"))
      (node (ref "J11") (pin "1") (pintype "passive"))
      (node (ref "J2") (pin "23") (pintype "passive"))
      (node (ref "J2") (pin "24") (pintype "passive"))
      (node (ref "J2") (pin "6") (pintype "passive"))
      (node (ref "J2") (pin "8") (pintype "passive"))
      (node (ref "J3") (pin "13") (pintype "passive"))
      (node (ref "J3") (pin "2") (pintype "passive"))
      (node (ref "J3") (pin "20") (pintype "passive"))
      (node (ref "J3") (pin "4") (pintype "passive"))
      (node (ref "J4") (pin "1") (pintype "passive"))
      (node (ref "J5") (pin "1") (pintype "passive"))
      (node (ref "J6") (pin "1") (pintype "passive"))
      (node (ref "J7") (pin "1") (pintype "passive"))
      (node (ref "J8") (pin "1") (pintype "passive"))
      (node (ref "J9") (pin "1") (pintype "passive"))
      (node (ref "R1") (pin "2") (pinfunction "2_2") (pintype "passive"))
      (node (ref "R10") (pin "2") (pinfunction "2_2") (pintype "passive"))
      (node (ref "R12") (pin "2") (pinfunction "2_2") (pintype "passive"))
      (node (ref "R8") (pin "2") (pinfunction "2_2") (pintype "passive"))
      (node (ref "U1") (pin "A11") (pinfunction "DGND_A11") (pintype "passive"))
      (node (ref "U1") (pin "B1") (pinfunction "DGND_B1") (pintype "passive"))
      (node (ref "U1") (pin "C2") (pinfunction "GND_ANA_PIX_0_C2") (pintype "passive"))
      (node (ref "U1") (pin "D4") (pinfunction "DGND_D4") (pintype "passive"))
      (node (ref "U1") (pin "D5") (pinfunction "DGND_D5") (pintype "passive"))
      (node (ref "U1") (pin "D6") (pinfunction "DGND_D6") (pintype "passive"))
      (node (ref "U1") (pin "D7") (pinfunction "DGND_D7") (pintype "passive"))
      (node (ref "U1") (pin "D8") (pinfunction "DGND_D8") (pintype "passive"))
      (node (ref "U1") (pin "E4") (pinfunction "DGND_E4") (pintype "passive"))
      (node (ref "U1") (pin "E5") (pinfunction "DGND_E5") (pintype "passive"))
      (node (ref "U1") (pin "E6") (pinfunction "DGND_E6") (pintype "passive"))
      (node (ref "U1") (pin "E7") (pinfunction "DGND_E7") (pintype "passive"))
      (node (ref "U1") (pin "E8") (pinfunction "DGND_E8") (pintype "passive"))
      (node (ref "U1") (pin "F2") (pinfunction "GND_DIG_ACORE_0_F2") (pintype "passive"))
      (node (ref "U1") (pin "F4") (pinfunction "DGND_F4") (pintype "passive"))
      (node (ref "U1") (pin "F5") (pinfunction "DGND_F5") (pintype "passive"))
      (node (ref "U1") (pin "F6") (pinfunction "DGND_F6") (pintype "passive"))
      (node (ref "U1") (pin "F7") (pinfunction "GND_ANA_ACORE_0_F7") (pintype "passive"))
      (node (ref "U1") (pin "F8") (pinfunction "GND_ANA_ACORE_1_F8") (pintype "passive"))
      (node (ref "U1") (pin "G2") (pinfunction "GND_ANA_PIX_1_G2") (pintype "passive"))
      (node (ref "U1") (pin "H2") (pinfunction "GND_ANA_ACORE_2_H2") (pintype "passive"))
      (node (ref "U1") (pin "H3") (pinfunction "GND_ANA_ACORE_3_H3") (pintype "passive"))
      (node (ref "U1") (pin "H5") (pinfunction "GND_DIG_ACORE_1_H5") (pintype "passive"))
      (node (ref "U1") (pin "J1") (pinfunction "DGND_J1") (pintype "passive"))
      (node (ref "U1") (pin "J11") (pinfunction "DGND_J11") (pintype "passive"))
      (node (ref "U1") (pin "J4") (pinfunction "GND_ANA_PIX_2_J4") (pintype "passive"))
      (node (ref "U1") (pin "J5") (pinfunction "TEST_J5") (pintype "passive"))
      (node (ref "U2") (pin "A11") (pinfunction "DGND_A11") (pintype "passive"))
      (node (ref "U2") (pin "B1") (pinfunction "DGND_B1") (pintype "passive"))
      (node (ref "U2") (pin "C2") (pinfunction "GND_ANA_PIX_0_C2") (pintype "passive"))
      (node (ref "U2") (pin "D4") (pinfunction "DGND_D4") (pintype "passive"))
      (node (ref "U2") (pin "D5") (pinfunction "DGND_D5") (pintype "passive"))
      (node (ref "U2") (pin "D6") (pinfunction "DGND_D6") (pintype "passive"))
      (node (ref "U2") (pin "D7") (pinfunction "DGND_D7") (pintype "passive"))
      (node (ref "U2") (pin "D8") (pinfunction "DGND_D8") (pintype "passive"))
      (node (ref "U2") (pin "E4") (pinfunction "DGND_E4") (pintype "passive"))
      (node (ref "U2") (pin "E5") (pinfunction "DGND_E5") (pintype "passive"))
      (node (ref "U2") (pin "E6") (pinfunction "DGND_E6") (pintype "passive"))
      (node (ref "U2") (pin "E7") (pinfunction "DGND_E7") (pintype "passive"))
      (node (ref "U2") (pin "E8") (pinfunction "DGND_E8") (pintype "passive"))
      (node (ref "U2") (pin "F2") (pinfunction "GND_DIG_ACORE_0_F2") (pintype "passive"))
      (node (ref "U2") (pin "F4") (pinfunction "DGND_F4") (pintype "passive"))
      (node (ref "U2") (pin "F5") (pinfunction "DGND_F5") (pintype "passive"))
      (node (ref "U2") (pin "F6") (pinfunction "DGND_F6") (pintype "passive"))
      (node (ref "U2") (pin "F7") (pinfunction "GND_ANA_ACORE_0_F7") (pintype "passive"))
      (node (ref "U2") (pin "F8") (pinfunction "GND_ANA_ACORE_1_F8") (pintype "passive"))
      (node (ref "U2") (pin "G2") (pinfunction "GND_ANA_PIX_1_G2") (pintype "passive"))
      (node (ref "U2") (pin "H2") (pinfunction "GND_ANA_ACORE_2_H2") (pintype "passive"))
      (node (ref "U2") (pin "H3") (pinfunction "GND_ANA_ACORE_3_H3") (pintype "passive"))
      (node (ref "U2") (pin "H5") (pinfunction "GND_DIG_ACORE_1_H5") (pintype "passive"))
      (node (ref "U2") (pin "J1") (pinfunction "DGND_J1") (pintype "passive"))
      (node (ref "U2") (pin "J11") (pinfunction "DGND_J11") (pintype "passive"))
      (node (ref "U2") (pin "J4") (pinfunction "GND_ANA_PIX_2_J4") (pintype "passive"))
      (node (ref "U2") (pin "J5") (pinfunction "TEST_J5") (pintype "passive"))
      (node (ref "U3") (pin "A11") (pinfunction "DGND_A11") (pintype "passive"))
      (node (ref "U3") (pin "B1") (pinfunction "DGND_B1") (pintype "passive"))
      (node (ref "U3") (pin "C2") (pinfunction "GND_ANA_PIX_0_C2") (pintype "passive"))
      (node (ref "U3") (pin "D4") (pinfunction "DGND_D4") (pintype "passive"))
      (node (ref "U3") (pin "D5") (pinfunction "DGND_D5") (pintype "passive"))
      (node (ref "U3") (pin "D6") (pinfunction "DGND_D6") (pintype "passive"))
      (node (ref "U3") (pin "D7") (pinfunction "DGND_D7") (pintype "passive"))
      (node (ref "U3") (pin "D8") (pinfunction "DGND_D8") (pintype "passive"))
      (node (ref "U3") (pin "E4") (pinfunction "DGND_E4") (pintype "passive"))
      (node (ref "U3") (pin "E5") (pinfunction "DGND_E5") (pintype "passive"))
      (node (ref "U3") (pin "E6") (pinfunction "DGND_E6") (pintype "passive"))
      (node (ref "U3") (pin "E7") (pinfunction "DGND_E7") (pintype "passive"))
      (node (ref "U3") (pin "E8") (pinfunction "DGND_E8") (pintype "passive"))
      (node (ref "U3") (pin "F2") (pinfunction "GND_DIG_ACORE_0_F2") (pintype "passive"))
      (node (ref "U3") (pin "F4") (pinfunction "DGND_F4") (pintype "passive"))
      (node (ref "U3") (pin "F5") (pinfunction "DGND_F5") (pintype "passive"))
      (node (ref "U3") (pin "F6") (pinfunction "DGND_F6") (pintype "passive"))
      (node (ref "U3") (pin "F7") (pinfunction "GND_ANA_ACORE_0_F7") (pintype "passive"))
      (node (ref "U3") (pin "F8") (pinfunction "GND_ANA_ACORE_1_F8") (pintype "passive"))
      (node (ref "U3") (pin "G2") (pinfunction "GND_ANA_PIX_1_G2") (pintype "passive"))
      (node (ref "U3") (pin "H2") (pinfunction "GND_ANA_ACORE_2_H2") (pintype "passive"))
      (node (ref "U3") (pin "H3") (pinfunction "GND_ANA_ACORE_3_H3") (pintype "passive"))
      (node (ref "U3") (pin "H5") (pinfunction "GND_DIG_ACORE_1_H5") (pintype "passive"))
      (node (ref "U3") (pin "J1") (pinfunction "DGND_J1") (pintype "passive"))
      (node (ref "U3") (pin "J11") (pinfunction "DGND_J11") (pintype "passive"))
      (node (ref "U3") (pin "J4") (pinfunction "GND_ANA_PIX_2_J4") (pintype "passive"))
      (node (ref "U3") (pin "J5") (pinfunction "TEST_J5") (pintype "passive"))
      (node (ref "U4") (pin "A11") (pinfunction "DGND_A11") (pintype "passive"))
      (node (ref "U4") (pin "B1") (pinfunction "DGND_B1") (pintype "passive"))
      (node (ref "U4") (pin "C2") (pinfunction "GND_ANA_PIX_0_C2") (pintype "passive"))
      (node (ref "U4") (pin "D4") (pinfunction "DGND_D4") (pintype "passive"))
      (node (ref "U4") (pin "D5") (pinfunction "DGND_D5") (pintype "passive"))
      (node (ref "U4") (pin "D6") (pinfunction "DGND_D6") (pintype "passive"))
      (node (ref "U4") (pin "D7") (pinfunction "DGND_D7") (pintype "passive"))
      (node (ref "U4") (pin "D8") (pinfunction "DGND_D8") (pintype "passive"))
      (node (ref "U4") (pin "E4") (pinfunction "DGND_E4") (pintype "passive"))
      (node (ref "U4") (pin "E5") (pinfunction "DGND_E5") (pintype "passive"))
      (node (ref "U4") (pin "E6") (pinfunction "DGND_E6") (pintype "passive"))
      (node (ref "U4") (pin "E7") (pinfunction "DGND_E7") (pintype "passive"))
      (node (ref "U4") (pin "E8") (pinfunction "DGND_E8") (pintype "passive"))
      (node (ref "U4") (pin "F2") (pinfunction "GND_DIG_ACORE_0_F2") (pintype "passive"))
      (node (ref "U4") (pin "F4") (pinfunction "DGND_F4") (pintype "passive"))
      (node (ref "U4") (pin "F5") (pinfunction "DGND_F5") (pintype "passive"))
      (node (ref "U4") (pin "F6") (pinfunction "DGND_F6") (pintype "passive"))
      (node (ref "U4") (pin "F7") (pinfunction "GND_ANA_ACORE_0_F7") (pintype "passive"))
      (node (ref "U4") (pin "F8") (pinfunction "GND_ANA_ACORE_1_F8") (pintype "passive"))
      (node (ref "U4") (pin "G2") (pinfunction "GND_ANA_PIX_1_G2") (pintype "passive"))
      (node (ref "U4") (pin "H2") (pinfunction "GND_ANA_ACORE_2_H2") (pintype "passive"))
      (node (ref "U4") (pin "H3") (pinfunction "GND_ANA_ACORE_3_H3") (pintype "passive"))
      (node (ref "U4") (pin "H5") (pinfunction "GND_DIG_ACORE_1_H5") (pintype "passive"))
      (node (ref "U4") (pin "J1") (pinfunction "DGND_J1") (pintype "passive"))
      (node (ref "U4") (pin "J11") (pinfunction "DGND_J11") (pintype "passive"))
      (node (ref "U4") (pin "J4") (pinfunction "GND_ANA_PIX_2_J4") (pintype "passive"))
      (node (ref "U4") (pin "J5") (pinfunction "TEST_J5") (pintype "passive"))
    )
    (net (code "46") (name "Net-(U1A-ATEST1)") (class "Default")
      (node (ref "J4") (pin "2") (pintype "passive"))
      (node (ref "U1") (pin "J8") (pinfunction "ATEST1_J8") (pintype "passive"))
    )
    (net (code "47") (name "Net-(U1A-ATEST2)") (class "Default")
      (node (ref "J8") (pin "2") (pintype "passive"))
      (node (ref "U1") (pin "C1") (pinfunction "ATEST2_C1") (pintype "passive"))
    )
    (net (code "48") (name "Net-(U1A-GPI3)") (class "Default")
      (node (ref "R2") (pin "2") (pinfunction "2_2") (pintype "passive"))
      (node (ref "U1") (pin "E2") (pinfunction "GPI3_E2") (pintype "passive"))
    )
    (net (code "49") (name "Net-(U2A-ATEST1)") (class "Default")
      (node (ref "J5") (pin "2") (pintype "passive"))
      (node (ref "U2") (pin "J8") (pinfunction "ATEST1_J8") (pintype "passive"))
    )
    (net (code "50") (name "Net-(U2A-ATEST2)") (class "Default")
      (node (ref "J9") (pin "2") (pintype "passive"))
      (node (ref "U2") (pin "C1") (pinfunction "ATEST2_C1") (pintype "passive"))
    )
    (net (code "51") (name "Net-(U2A-GPI3)") (class "Default")
      (node (ref "R3") (pin "2") (pinfunction "2_2") (pintype "passive"))
      (node (ref "U2") (pin "E2") (pinfunction "GPI3_E2") (pintype "passive"))
    )
    (net (code "52") (name "Net-(U3A-ATEST1)") (class "Default")
      (node (ref "J6") (pin "2") (pintype "passive"))
      (node (ref "U3") (pin "J8") (pinfunction "ATEST1_J8") (pintype "passive"))
    )
    (net (code "53") (name "Net-(U3A-ATEST2)") (class "Default")
      (node (ref "J10") (pin "2") (pintype "passive"))
      (node (ref "U3") (pin "C1") (pinfunction "ATEST2_C1") (pintype "passive"))
    )
    (net (code "54") (name "Net-(U3A-GPI3)") (class "Default")
      (node (ref "R4") (pin "2") (pinfunction "2_2") (pintype "passive"))
      (node (ref "U3") (pin "E2") (pinfunction "GPI3_E2") (pintype "passive"))
    )
    (net (code "55") (name "Net-(U4A-ATEST1)") (class "Default")
      (node (ref "J7") (pin "2") (pintype "passive"))
      (node (ref "U4") (pin "J8") (pinfunction "ATEST1_J8") (pintype "passive"))
    )
    (net (code "56") (name "Net-(U4A-ATEST2)") (class "Default")
      (node (ref "J11") (pin "2") (pintype "passive"))
      (node (ref "U4") (pin "C1") (pinfunction "ATEST2_C1") (pintype "passive"))
    )
    (net (code "57") (name "Net-(U4A-GPI3)") (class "Default")
      (node (ref "R5") (pin "2") (pinfunction "2_2") (pintype "passive"))
      (node (ref "U4") (pin "E2") (pinfunction "GPI3_E2") (pintype "passive"))
    )
    (net (code "58") (name "unconnected-(H1-Pad1)") (class "Default")
      (node (ref "H1") (pin "1") (pinfunction "1_1") (pintype "power_in"))
    )
    (net (code "59") (name "unconnected-(H2-Pad1)") (class "Default")
      (node (ref "H2") (pin "1") (pinfunction "1_1") (pintype "power_in"))
    )
    (net (code "60") (name "unconnected-(H3-Pad1)") (class "Default")
      (node (ref "H3") (pin "1") (pinfunction "1_1") (pintype "power_in"))
    )
    (net (code "61") (name "unconnected-(H4-Pad1)") (class "Default")
      (node (ref "H4") (pin "1") (pinfunction "1_1") (pintype "power_in"))
    )
    (net (code "62") (name "unconnected-(J1-Pad8)") (class "Default")
      (node (ref "J1") (pin "8") (pinfunction "8_8") (pintype "passive"))
    )
    (net (code "63") (name "unconnected-(J1-Pad9)") (class "Default")
      (node (ref "J1") (pin "9") (pinfunction "9_9") (pintype "passive"))
    )
    (net (code "64") (name "unconnected-(U1A-DATA3N-PadB5)") (class "Default")
      (node (ref "U1") (pin "B5") (pinfunction "DATA3N_B5") (pintype "passive"))
    )
    (net (code "65") (name "unconnected-(U1A-DATA3P-PadA5)") (class "Default")
      (node (ref "U1") (pin "A5") (pinfunction "DATA3P_A5") (pintype "passive"))
    )
    (net (code "66") (name "unconnected-(U1A-DATA4N-PadB4)") (class "Default")
      (node (ref "U1") (pin "B4") (pinfunction "DATA4N_B4") (pintype "passive"))
    )
    (net (code "67") (name "unconnected-(U1A-DATA4P-PadA4)") (class "Default")
      (node (ref "U1") (pin "A4") (pinfunction "DATA4P_A4") (pintype "passive"))
    )
    (net (code "68") (name "unconnected-(U1A-P1_CLKN-PadE10)") (class "Default")
      (node (ref "U1") (pin "E10") (pinfunction "P1_CLKN_E10") (pintype "passive"))
    )
    (net (code "69") (name "unconnected-(U1A-P1_CLKP-PadE11)") (class "Default")
      (node (ref "U1") (pin "E11") (pinfunction "P1_CLKP_E11") (pintype "passive"))
    )
    (net (code "70") (name "unconnected-(U1A-P1_DATA2N-PadD10)") (class "Default")
      (node (ref "U1") (pin "D10") (pinfunction "P1_DATA2N_D10") (pintype "passive"))
    )
    (net (code "71") (name "unconnected-(U1A-P1_DATA2P-PadD11)") (class "Default")
      (node (ref "U1") (pin "D11") (pinfunction "P1_DATA2P_D11") (pintype "passive"))
    )
    (net (code "72") (name "unconnected-(U1A-P1_DATA3N-PadF10)") (class "Default")
      (node (ref "U1") (pin "F10") (pinfunction "P1_DATA3N_F10") (pintype "passive"))
    )
    (net (code "73") (name "unconnected-(U1A-P1_DATA3P-PadF11)") (class "Default")
      (node (ref "U1") (pin "F11") (pinfunction "P1_DATA3P_F11") (pintype "passive"))
    )
    (net (code "74") (name "unconnected-(U1A-P1_DATA4N-PadG10)") (class "Default")
      (node (ref "U1") (pin "G10") (pinfunction "P1_DATA4N_G10") (pintype "passive"))
    )
    (net (code "75") (name "unconnected-(U1A-P1_DATA4P-PadG11)") (class "Default")
      (node (ref "U1") (pin "G11") (pinfunction "P1_DATA4P_G11") (pintype "passive"))
    )
    (net (code "76") (name "unconnected-(U1A-P1_DATAN-PadC10)") (class "Default")
      (node (ref "U1") (pin "C10") (pinfunction "P1_DATAN_C10") (pintype "passive"))
    )
    (net (code "77") (name "unconnected-(U1A-P1_DATAP-PadC11)") (class "Default")
      (node (ref "U1") (pin "C11") (pinfunction "P1_DATAP_C11") (pintype "passive"))
    )
    (net (code "78") (name "unconnected-(U2A-DATA3N-PadB5)") (class "Default")
      (node (ref "U2") (pin "B5") (pinfunction "DATA3N_B5") (pintype "passive"))
    )
    (net (code "79") (name "unconnected-(U2A-DATA3P-PadA5)") (class "Default")
      (node (ref "U2") (pin "A5") (pinfunction "DATA3P_A5") (pintype "passive"))
    )
    (net (code "80") (name "unconnected-(U2A-DATA4N-PadB4)") (class "Default")
      (node (ref "U2") (pin "B4") (pinfunction "DATA4N_B4") (pintype "passive"))
    )
    (net (code "81") (name "unconnected-(U2A-DATA4P-PadA4)") (class "Default")
      (node (ref "U2") (pin "A4") (pinfunction "DATA4P_A4") (pintype "passive"))
    )
    (net (code "82") (name "unconnected-(U2A-P1_CLKN-PadE10)") (class "Default")
      (node (ref "U2") (pin "E10") (pinfunction "P1_CLKN_E10") (pintype "passive"))
    )
    (net (code "83") (name "unconnected-(U2A-P1_CLKP-PadE11)") (class "Default")
      (node (ref "U2") (pin "E11") (pinfunction "P1_CLKP_E11") (pintype "passive"))
    )
    (net (code "84") (name "unconnected-(U2A-P1_DATA2N-PadD10)") (class "Default")
      (node (ref "U2") (pin "D10") (pinfunction "P1_DATA2N_D10") (pintype "passive"))
    )
    (net (code "85") (name "unconnected-(U2A-P1_DATA2P-PadD11)") (class "Default")
      (node (ref "U2") (pin "D11") (pinfunction "P1_DATA2P_D11") (pintype "passive"))
    )
    (net (code "86") (name "unconnected-(U2A-P1_DATA3N-PadF10)") (class "Default")
      (node (ref "U2") (pin "F10") (pinfunction "P1_DATA3N_F10") (pintype "passive"))
    )
    (net (code "87") (name "unconnected-(U2A-P1_DATA3P-PadF11)") (class "Default")
      (node (ref "U2") (pin "F11") (pinfunction "P1_DATA3P_F11") (pintype "passive"))
    )
    (net (code "88") (name "unconnected-(U2A-P1_DATA4N-PadG10)") (class "Default")
      (node (ref "U2") (pin "G10") (pinfunction "P1_DATA4N_G10") (pintype "passive"))
    )
    (net (code "89") (name "unconnected-(U2A-P1_DATA4P-PadG11)") (class "Default")
      (node (ref "U2") (pin "G11") (pinfunction "P1_DATA4P_G11") (pintype "passive"))
    )
    (net (code "90") (name "unconnected-(U2A-P1_DATAN-PadC10)") (class "Default")
      (node (ref "U2") (pin "C10") (pinfunction "P1_DATAN_C10") (pintype "passive"))
    )
    (net (code "91") (name "unconnected-(U2A-P1_DATAP-PadC11)") (class "Default")
      (node (ref "U2") (pin "C11") (pinfunction "P1_DATAP_C11") (pintype "passive"))
    )
    (net (code "92") (name "unconnected-(U3A-DATA3N-PadB5)") (class "Default")
      (node (ref "U3") (pin "B5") (pinfunction "DATA3N_B5") (pintype "passive"))
    )
    (net (code "93") (name "unconnected-(U3A-DATA3P-PadA5)") (class "Default")
      (node (ref "U3") (pin "A5") (pinfunction "DATA3P_A5") (pintype "passive"))
    )
    (net (code "94") (name "unconnected-(U3A-DATA4N-PadB4)") (class "Default")
      (node (ref "U3") (pin "B4") (pinfunction "DATA4N_B4") (pintype "passive"))
    )
    (net (code "95") (name "unconnected-(U3A-DATA4P-PadA4)") (class "Default")
      (node (ref "U3") (pin "A4") (pinfunction "DATA4P_A4") (pintype "passive"))
    )
    (net (code "96") (name "unconnected-(U3A-P1_CLKN-PadE10)") (class "Default")
      (node (ref "U3") (pin "E10") (pinfunction "P1_CLKN_E10") (pintype "passive"))
    )
    (net (code "97") (name "unconnected-(U3A-P1_CLKP-PadE11)") (class "Default")
      (node (ref "U3") (pin "E11") (pinfunction "P1_CLKP_E11") (pintype "passive"))
    )
    (net (code "98") (name "unconnected-(U3A-P1_DATA2N-PadD10)") (class "Default")
      (node (ref "U3") (pin "D10") (pinfunction "P1_DATA2N_D10") (pintype "passive"))
    )
    (net (code "99") (name "unconnected-(U3A-P1_DATA2P-PadD11)") (class "Default")
      (node (ref "U3") (pin "D11") (pinfunction "P1_DATA2P_D11") (pintype "passive"))
    )
    (net (code "100") (name "unconnected-(U3A-P1_DATA3N-PadF10)") (class "Default")
      (node (ref "U3") (pin "F10") (pinfunction "P1_DATA3N_F10") (pintype "passive"))
    )
    (net (code "101") (name "unconnected-(U3A-P1_DATA3P-PadF11)") (class "Default")
      (node (ref "U3") (pin "F11") (pinfunction "P1_DATA3P_F11") (pintype "passive"))
    )
    (net (code "102") (name "unconnected-(U3A-P1_DATA4N-PadG10)") (class "Default")
      (node (ref "U3") (pin "G10") (pinfunction "P1_DATA4N_G10") (pintype "passive"))
    )
    (net (code "103") (name "unconnected-(U3A-P1_DATA4P-PadG11)") (class "Default")
      (node (ref "U3") (pin "G11") (pinfunction "P1_DATA4P_G11") (pintype "passive"))
    )
    (net (code "104") (name "unconnected-(U3A-P1_DATAN-PadC10)") (class "Default")
      (node (ref "U3") (pin "C10") (pinfunction "P1_DATAN_C10") (pintype "passive"))
    )
    (net (code "105") (name "unconnected-(U3A-P1_DATAP-PadC11)") (class "Default")
      (node (ref "U3") (pin "C11") (pinfunction "P1_DATAP_C11") (pintype "passive"))
    )
    (net (code "106") (name "unconnected-(U4A-DATA3N-PadB5)") (class "Default")
      (node (ref "U4") (pin "B5") (pinfunction "DATA3N_B5") (pintype "passive"))
    )
    (net (code "107") (name "unconnected-(U4A-DATA3P-PadA5)") (class "Default")
      (node (ref "U4") (pin "A5") (pinfunction "DATA3P_A5") (pintype "passive"))
    )
    (net (code "108") (name "unconnected-(U4A-DATA4N-PadB4)") (class "Default")
      (node (ref "U4") (pin "B4") (pinfunction "DATA4N_B4") (pintype "passive"))
    )
    (net (code "109") (name "unconnected-(U4A-DATA4P-PadA4)") (class "Default")
      (node (ref "U4") (pin "A4") (pinfunction "DATA4P_A4") (pintype "passive"))
    )
    (net (code "110") (name "unconnected-(U4A-P1_CLKN-PadE10)") (class "Default")
      (node (ref "U4") (pin "E10") (pinfunction "P1_CLKN_E10") (pintype "passive"))
    )
    (net (code "111") (name "unconnected-(U4A-P1_CLKP-PadE11)") (class "Default")
      (node (ref "U4") (pin "E11") (pinfunction "P1_CLKP_E11") (pintype "passive"))
    )
    (net (code "112") (name "unconnected-(U4A-P1_DATA2N-PadD10)") (class "Default")
      (node (ref "U4") (pin "D10") (pinfunction "P1_DATA2N_D10") (pintype "passive"))
    )
    (net (code "113") (name "unconnected-(U4A-P1_DATA2P-PadD11)") (class "Default")
      (node (ref "U4") (pin "D11") (pinfunction "P1_DATA2P_D11") (pintype "passive"))
    )
    (net (code "114") (name "unconnected-(U4A-P1_DATA3N-PadF10)") (class "Default")
      (node (ref "U4") (pin "F10") (pinfunction "P1_DATA3N_F10") (pintype "passive"))
    )
    (net (code "115") (name "unconnected-(U4A-P1_DATA3P-PadF11)") (class "Default")
      (node (ref "U4") (pin "F11") (pinfunction "P1_DATA3P_F11") (pintype "passive"))
    )
    (net (code "116") (name "unconnected-(U4A-P1_DATA4N-PadG10)") (class "Default")
      (node (ref "U4") (pin "G10") (pinfunction "P1_DATA4N_G10") (pintype "passive"))
    )
    (net (code "117") (name "unconnected-(U4A-P1_DATA4P-PadG11)") (class "Default")
      (node (ref "U4") (pin "G11") (pinfunction "P1_DATA4P_G11") (pintype "passive"))
    )
    (net (code "118") (name "unconnected-(U4A-P1_DATAN-PadC10)") (class "Default")
      (node (ref "U4") (pin "C10") (pinfunction "P1_DATAN_C10") (pintype "passive"))
    )
    (net (code "119") (name "unconnected-(U4A-P1_DATAP-PadC11)") (class "Default")
      (node (ref "U4") (pin "C11") (pinfunction "P1_DATAP_C11") (pintype "passive"))
    )
  )
)
